# interfaceBoard.net
KiCad netlist of a schematic drawn in EAGLE
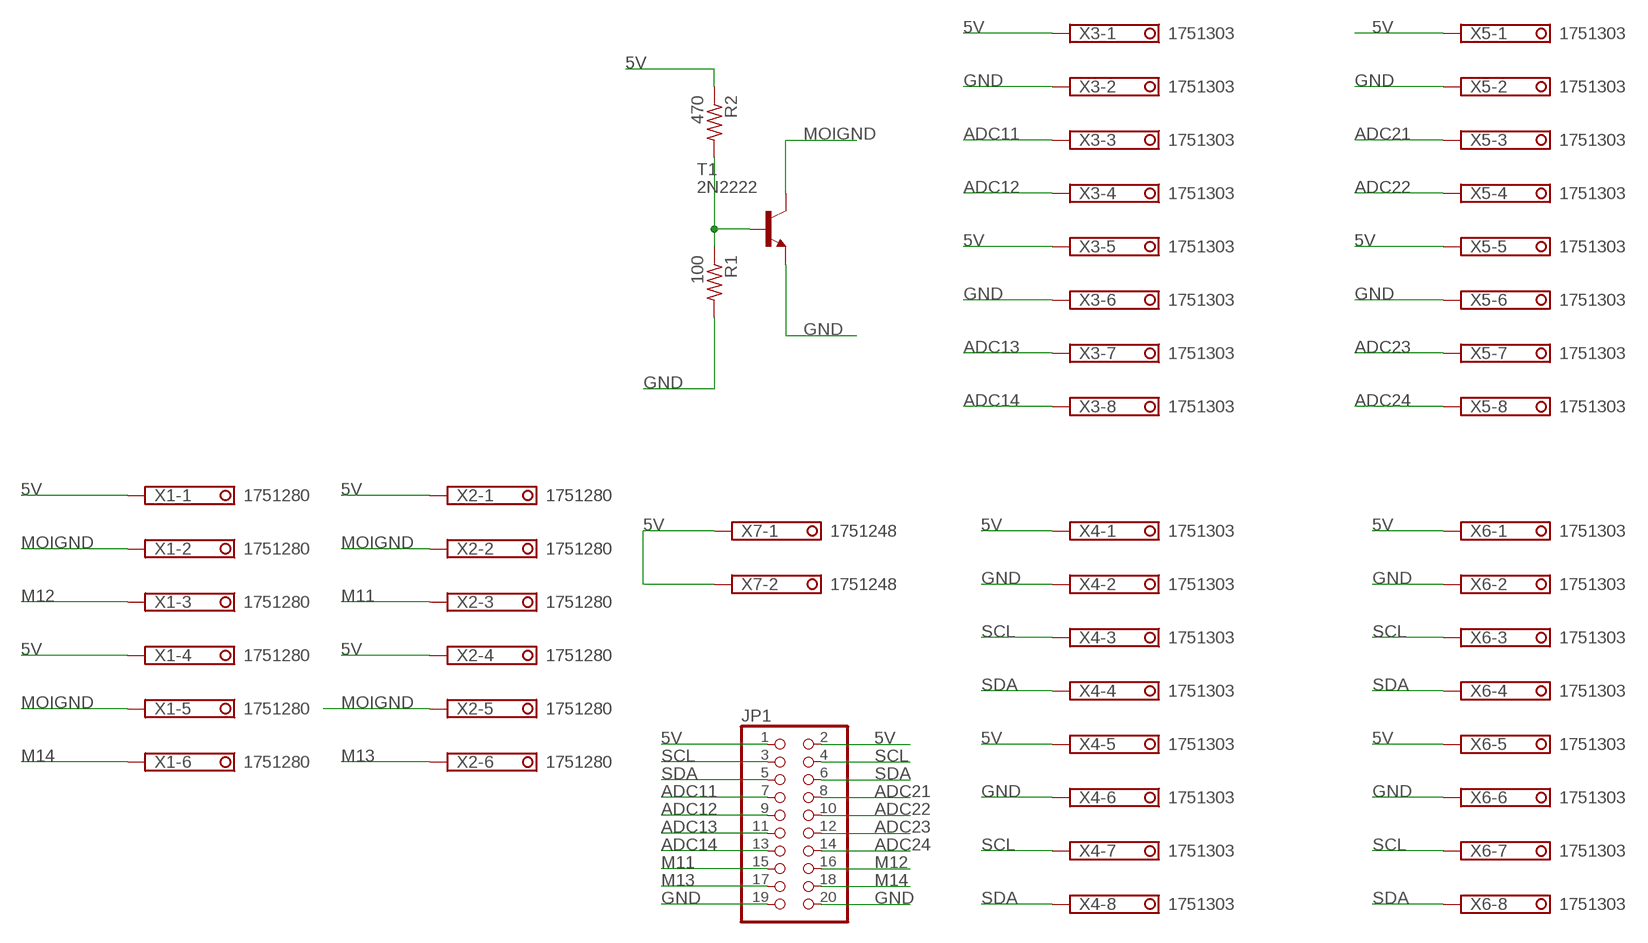
[diagram p0: schematic, sheet 1]

(export (version "E")
  (design (tool "Eeschema 10.0.6"))
  (components
    (comp (ref "JP1")
      (value "PINHD-2X10")
      (footprint "eagle-import:2X10")
      (libsource (lib "eagle-import") (part "PINHD-2X10"))
    )
    (comp (ref "R1")
      (value "100")
      (footprint "eagle-import:M0805")
      (libsource (lib "eagle-import") (part "R-US_M0805"))
    )
    (comp (ref "R2")
      (value "470")
      (footprint "eagle-import:M0805")
      (libsource (lib "eagle-import") (part "R-US_M0805"))
    )
    (comp (ref "T1")
      (value "2N2222")
      (footprint "eagle-import:TO92-EBC-OVAL")
      (libsource (lib "eagle-import") (part "2N2222"))
    )
    (comp (ref "X1")
      (value "1751280")
      (footprint "eagle-import:1751280")
      (libsource (lib "eagle-import") (part "1751280"))
    )
    (comp (ref "X2")
      (value "1751280")
      (footprint "eagle-import:1751280")
      (libsource (lib "eagle-import") (part "1751280"))
    )
    (comp (ref "X3")
      (value "1751303")
      (footprint "eagle-import:1751303")
      (libsource (lib "eagle-import") (part "1751303"))
    )
    (comp (ref "X4")
      (value "1751303")
      (footprint "eagle-import:1751303")
      (libsource (lib "eagle-import") (part "1751303"))
    )
    (comp (ref "X5")
      (value "1751303")
      (footprint "eagle-import:1751303")
      (libsource (lib "eagle-import") (part "1751303"))
    )
    (comp (ref "X6")
      (value "1751303")
      (footprint "eagle-import:1751303")
      (libsource (lib "eagle-import") (part "1751303"))
    )
    (comp (ref "X7")
      (value "1751248")
      (footprint "eagle-import:1751248")
      (libsource (lib "eagle-import") (part "1751248"))
    )
  )
  (nets
    (net (code "1") (name "/5V") (class "Default")
      (node (ref "JP1") (pin "1") (pinfunction "1_1") (pintype "passive"))
      (node (ref "JP1") (pin "2") (pinfunction "2_2") (pintype "passive"))
      (node (ref "R2") (pin "1") (pinfunction "1_1") (pintype "passive"))
      (node (ref "X1") (pin "1") (pinfunction "K_1") (pintype "passive"))
      (node (ref "X1") (pin "4") (pinfunction "K_4") (pintype "passive"))
      (node (ref "X2") (pin "1") (pinfunction "K_1") (pintype "passive"))
      (node (ref "X2") (pin "4") (pinfunction "K_4") (pintype "passive"))
      (node (ref "X3") (pin "1") (pinfunction "K_1") (pintype "passive"))
      (node (ref "X3") (pin "5") (pinfunction "K_5") (pintype "passive"))
      (node (ref "X4") (pin "1") (pinfunction "K_1") (pintype "passive"))
      (node (ref "X4") (pin "5") (pinfunction "K_5") (pintype "passive"))
      (node (ref "X5") (pin "1") (pinfunction "K_1") (pintype "passive"))
      (node (ref "X5") (pin "5") (pinfunction "K_5") (pintype "passive"))
      (node (ref "X6") (pin "1") (pinfunction "K_1") (pintype "passive"))
      (node (ref "X6") (pin "5") (pinfunction "K_5") (pintype "passive"))
      (node (ref "X7") (pin "1") (pinfunction "K_1") (pintype "passive"))
      (node (ref "X7") (pin "2") (pinfunction "K_2") (pintype "passive"))
    )
    (net (code "2") (name "/ADC11") (class "Default")
      (node (ref "JP1") (pin "7") (pinfunction "7_7") (pintype "passive"))
      (node (ref "X3") (pin "3") (pinfunction "K_3") (pintype "passive"))
    )
    (net (code "3") (name "/ADC12") (class "Default")
      (node (ref "JP1") (pin "9") (pinfunction "9_9") (pintype "passive"))
      (node (ref "X3") (pin "4") (pinfunction "K_4") (pintype "passive"))
    )
    (net (code "4") (name "/ADC13") (class "Default")
      (node (ref "JP1") (pin "11") (pinfunction "11_11") (pintype "passive"))
      (node (ref "X3") (pin "7") (pinfunction "K_7") (pintype "passive"))
    )
    (net (code "5") (name "/ADC14") (class "Default")
      (node (ref "JP1") (pin "13") (pinfunction "13_13") (pintype "passive"))
      (node (ref "X3") (pin "8") (pinfunction "K_8") (pintype "passive"))
    )
    (net (code "6") (name "/ADC21") (class "Default")
      (node (ref "JP1") (pin "8") (pinfunction "8_8") (pintype "passive"))
      (node (ref "X5") (pin "3") (pinfunction "K_3") (pintype "passive"))
    )
    (net (code "7") (name "/ADC22") (class "Default")
      (node (ref "JP1") (pin "10") (pinfunction "10_10") (pintype "passive"))
      (node (ref "X5") (pin "4") (pinfunction "K_4") (pintype "passive"))
    )
    (net (code "8") (name "/ADC23") (class "Default")
      (node (ref "JP1") (pin "12") (pinfunction "12_12") (pintype "passive"))
      (node (ref "X5") (pin "7") (pinfunction "K_7") (pintype "passive"))
    )
    (net (code "9") (name "/ADC24") (class "Default")
      (node (ref "JP1") (pin "14") (pinfunction "14_14") (pintype "passive"))
      (node (ref "X5") (pin "8") (pinfunction "K_8") (pintype "passive"))
    )
    (net (code "10") (name "/GND") (class "Default")
      (node (ref "JP1") (pin "19") (pinfunction "19_19") (pintype "passive"))
      (node (ref "JP1") (pin "20") (pinfunction "20_20") (pintype "passive"))
      (node (ref "R1") (pin "2") (pinfunction "2_2") (pintype "passive"))
      (node (ref "T1") (pin "E") (pinfunction "E_E") (pintype "passive"))
      (node (ref "X3") (pin "2") (pinfunction "K_2") (pintype "passive"))
      (node (ref "X3") (pin "6") (pinfunction "K_6") (pintype "passive"))
      (node (ref "X4") (pin "2") (pinfunction "K_2") (pintype "passive"))
      (node (ref "X4") (pin "6") (pinfunction "K_6") (pintype "passive"))
      (node (ref "X5") (pin "2") (pinfunction "K_2") (pintype "passive"))
      (node (ref "X5") (pin "6") (pinfunction "K_6") (pintype "passive"))
      (node (ref "X6") (pin "2") (pinfunction "K_2") (pintype "passive"))
      (node (ref "X6") (pin "6") (pinfunction "K_6") (pintype "passive"))
    )
    (net (code "11") (name "/M11") (class "Default")
      (node (ref "JP1") (pin "15") (pinfunction "15_15") (pintype "passive"))
      (node (ref "X2") (pin "3") (pinfunction "K_3") (pintype "passive"))
    )
    (net (code "12") (name "/M12") (class "Default")
      (node (ref "JP1") (pin "16") (pinfunction "16_16") (pintype "passive"))
      (node (ref "X1") (pin "3") (pinfunction "K_3") (pintype "passive"))
    )
    (net (code "13") (name "/M13") (class "Default")
      (node (ref "JP1") (pin "17") (pinfunction "17_17") (pintype "passive"))
      (node (ref "X2") (pin "6") (pinfunction "K_6") (pintype "passive"))
    )
    (net (code "14") (name "/M14") (class "Default")
      (node (ref "JP1") (pin "18") (pinfunction "18_18") (pintype "passive"))
      (node (ref "X1") (pin "6") (pinfunction "K_6") (pintype "passive"))
    )
    (net (code "15") (name "/MOIGND") (class "Default")
      (node (ref "T1") (pin "C") (pinfunction "C_C") (pintype "passive"))
      (node (ref "X1") (pin "2") (pinfunction "K_2") (pintype "passive"))
      (node (ref "X1") (pin "5") (pinfunction "K_5") (pintype "passive"))
      (node (ref "X2") (pin "2") (pinfunction "K_2") (pintype "passive"))
      (node (ref "X2") (pin "5") (pinfunction "K_5") (pintype "passive"))
    )
    (net (code "16") (name "/SCL") (class "Default")
      (node (ref "JP1") (pin "3") (pinfunction "3_3") (pintype "passive"))
      (node (ref "JP1") (pin "4") (pinfunction "4_4") (pintype "passive"))
      (node (ref "X4") (pin "3") (pinfunction "K_3") (pintype "passive"))
      (node (ref "X4") (pin "7") (pinfunction "K_7") (pintype "passive"))
      (node (ref "X6") (pin "3") (pinfunction "K_3") (pintype "passive"))
      (node (ref "X6") (pin "7") (pinfunction "K_7") (pintype "passive"))
    )
    (net (code "17") (name "/SDA") (class "Default")
      (node (ref "JP1") (pin "5") (pinfunction "5_5") (pintype "passive"))
      (node (ref "JP1") (pin "6") (pinfunction "6_6") (pintype "passive"))
      (node (ref "X4") (pin "4") (pinfunction "K_4") (pintype "passive"))
      (node (ref "X4") (pin "8") (pinfunction "K_8") (pintype "passive"))
      (node (ref "X6") (pin "4") (pinfunction "K_4") (pintype "passive"))
      (node (ref "X6") (pin "8") (pinfunction "K_8") (pintype "passive"))
    )
    (net (code "18") (name "Net-(R1-Pad1)") (class "Default")
      (node (ref "R1") (pin "1") (pinfunction "1_1") (pintype "passive"))
      (node (ref "R2") (pin "2") (pinfunction "2_2") (pintype "passive"))
      (node (ref "T1") (pin "B") (pinfunction "B_B") (pintype "passive"))
    )
  )
)
